# Schematic_Rev3_1.net
KiCad netlist of a schematic drawn in Altium Designer
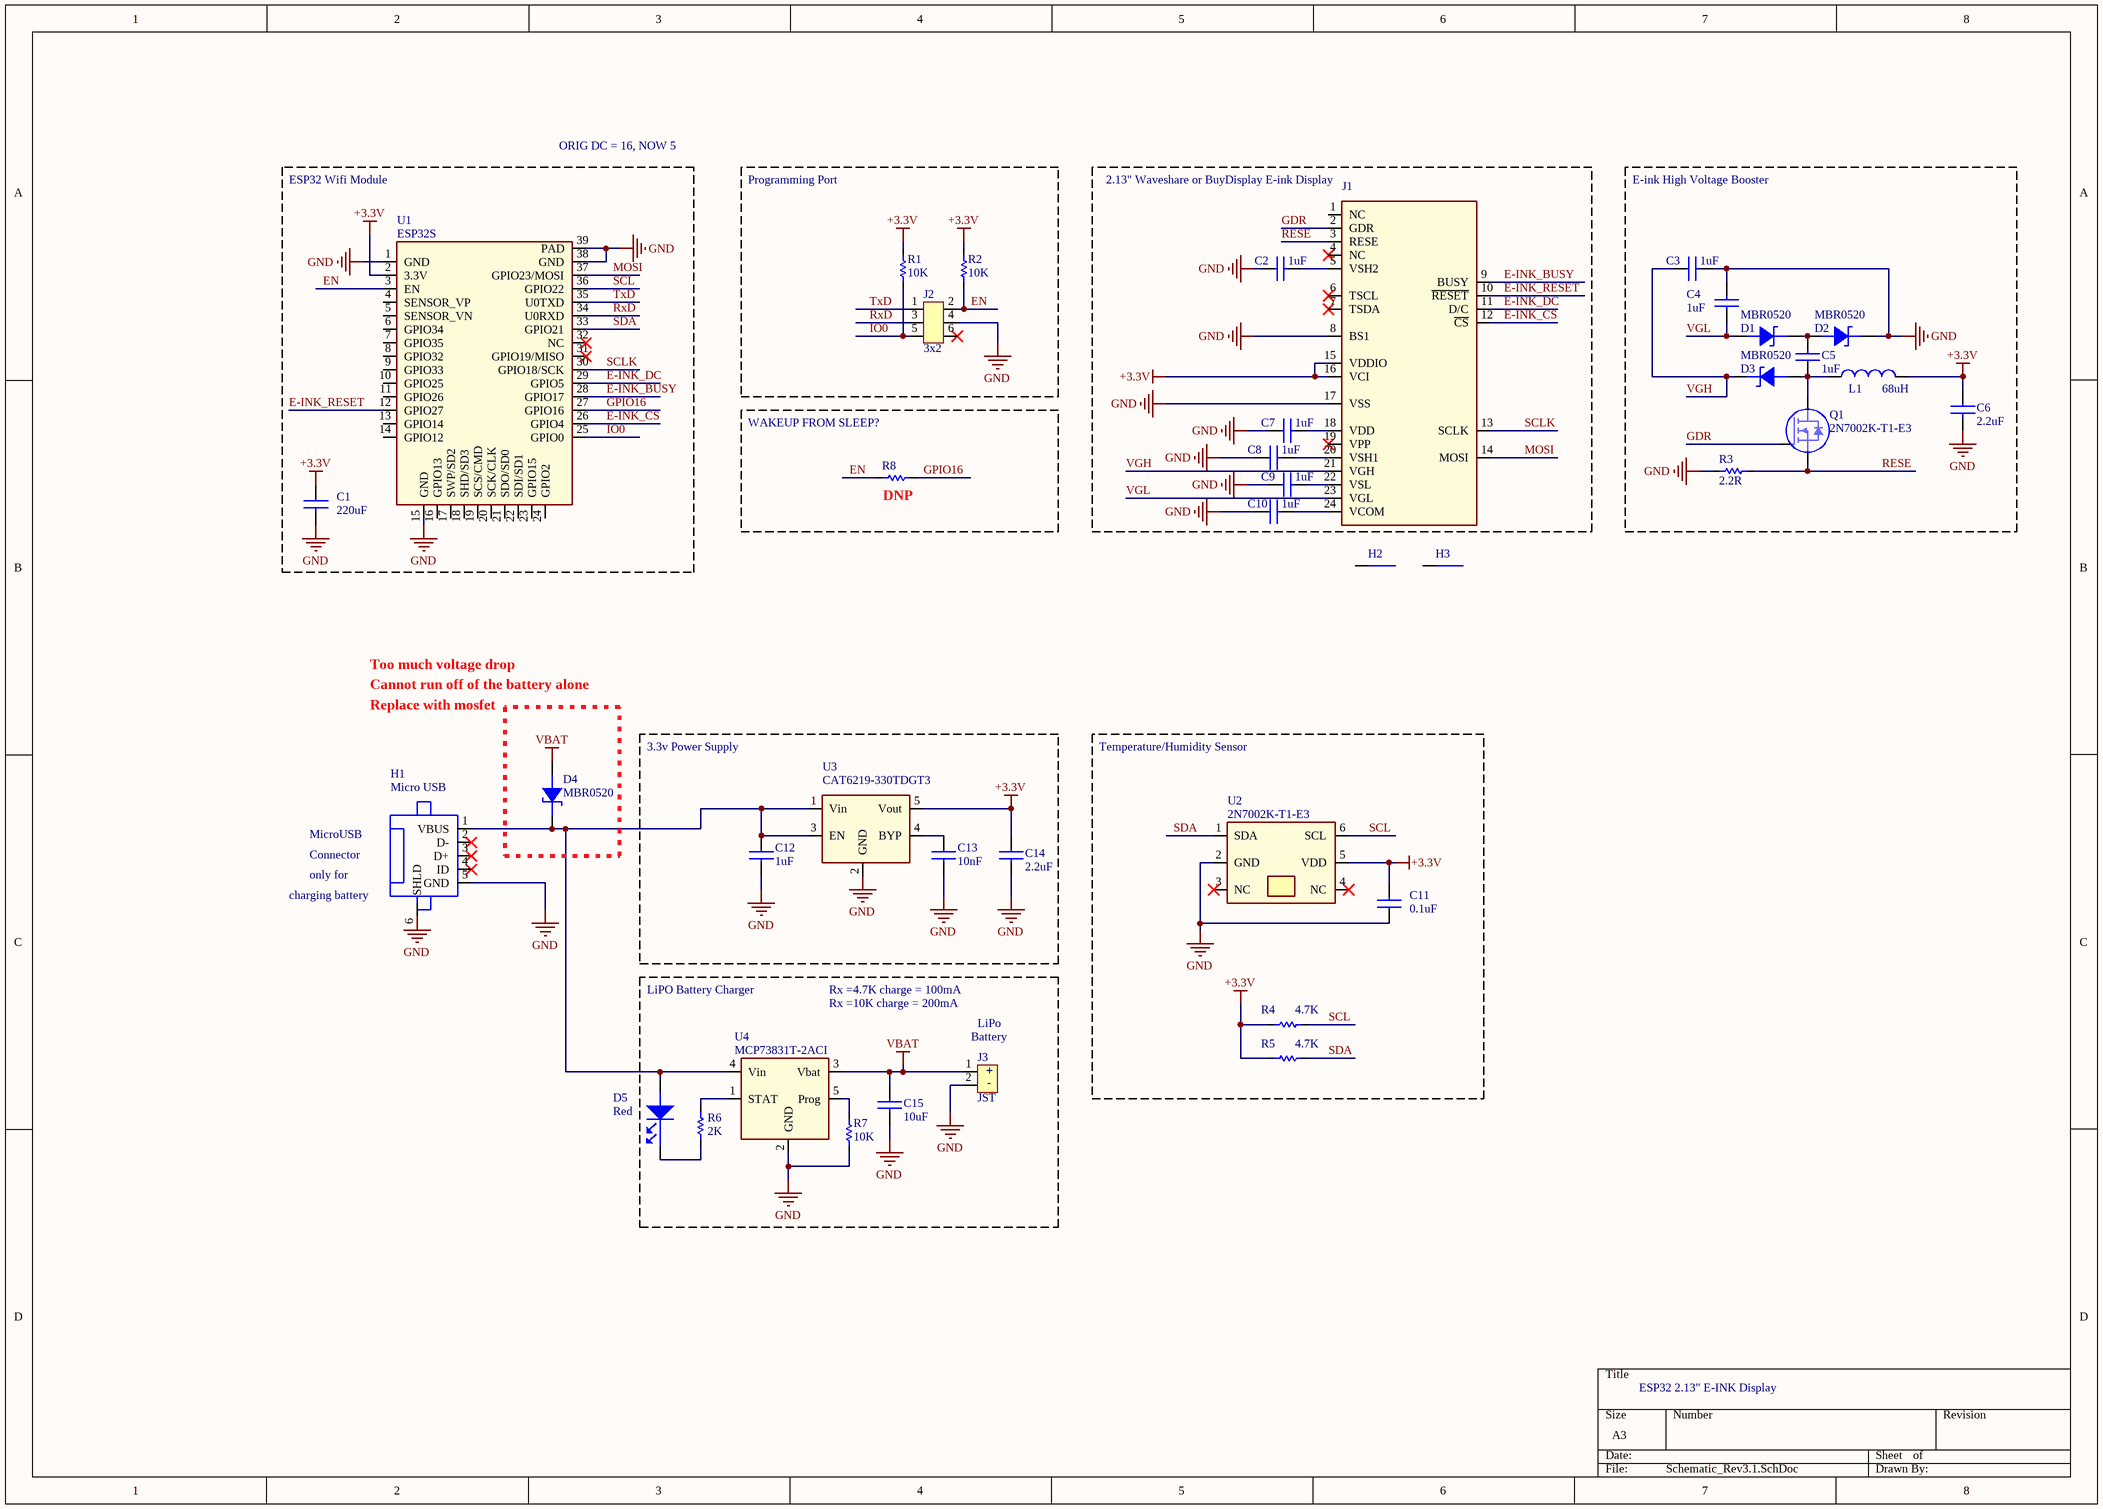
[diagram p0: Schematic_Rev3.1.SchDoc]

(export (version "E")
  (design (tool "Eeschema 10.0.6"))
  (components
    (comp (ref "C1")
      (value "220uF")
      (footprint "CAPC3216X160N")
      (description "CAP CER 220UF 4V X6S 1206")
      (fields (field (name "PARTNUMBER") "GRM31CC80G227ME11L") (field (name "MANUFACTURER") "Murata"))
      (libsource (lib "MAR") (part "CAP_1206"))
    )
    (comp (ref "C2")
      (value "1uF")
      (footprint "CAPC1608X09L")
      (description "CAP CER 1uF 16V X7R 0603")
      (fields (field (name "PARTNUMBER") "GRM188R71C105KA12D") (field (name "MANUFACTURER") "Murata"))
      (libsource (lib "MAR") (part "CAP_0603"))
    )
    (comp (ref "C3")
      (value "1uF")
      (footprint "CAPC1608X09L")
      (description "CAP CER 1UF 25V X7R 0603")
      (fields (field (name "PARTNUMBER") "C0603C105K3RACTU") (field (name "MANUFACTURER") "Kemet"))
      (libsource (lib "MAR") (part "CAP_0603"))
    )
    (comp (ref "C4")
      (value "1uF")
      (footprint "CAPC1608X09L")
      (description "CAP CER 1UF 25V X7R 0603")
      (fields (field (name "PARTNUMBER") "GRM188R71C105KA12D") (field (name "MANUFACTURER") "Kemet"))
      (libsource (lib "MAR") (part "CAP_0603"))
    )
    (comp (ref "C5")
      (value "1uF")
      (footprint "CAPC1608X09L")
      (description "CAP CER 1UF 25V X7R 0603")
      (fields (field (name "PARTNUMBER") "C0603C105K3RACTU") (field (name "MANUFACTURER") "Kemet"))
      (libsource (lib "MAR") (part "CAP_0603"))
    )
    (comp (ref "C6")
      (value "2.2uF")
      (footprint "CAPC1608X09L")
      (description "CAP CER 2.2uF 16V X5R 0603")
      (fields (field (name "MANUFACTURER") "Murata") (field (name "PARTNUMBER") "GRM188R61C225KE15D"))
      (libsource (lib "MAR") (part "CAP_0805"))
    )
    (comp (ref "C7")
      (value "1uF")
      (footprint "CAPC1608X09L")
      (description "CAP CER 1uF 16V X7R 0603")
      (fields (field (name "PARTNUMBER") "GRM188R71C105KA12D") (field (name "MANUFACTURER") "Murata"))
      (libsource (lib "MAR") (part "CAP_0603"))
    )
    (comp (ref "C8")
      (value "1uF")
      (footprint "CAPC1608X09L")
      (description "CAP CER 1uF 16V X7R 0603")
      (fields (field (name "PARTNUMBER") "GRM188R71C105KA12D") (field (name "MANUFACTURER") "Murata"))
      (libsource (lib "MAR") (part "CAP_0603"))
    )
    (comp (ref "C9")
      (value "1uF")
      (footprint "CAPC1608X09L")
      (description "CAP CER 1uF 16V X7R 0603")
      (fields (field (name "PARTNUMBER") "GRM188R71C105KA12D") (field (name "MANUFACTURER") "Murata"))
      (libsource (lib "MAR") (part "CAP_0603"))
    )
    (comp (ref "C10")
      (value "1uF")
      (footprint "CAPC1608X09L")
      (description "CAP CER 1uF 16V X7R 0603")
      (fields (field (name "PARTNUMBER") "GRM188R71C105KA12D") (field (name "MANUFACTURER") "Murata"))
      (libsource (lib "MAR") (part "CAP_0603"))
    )
    (comp (ref "C11")
      (value "0.1uF")
      (footprint "CAPC1608X09L")
      (description "CAP, 0.1uF, 25V, 0603")
      (fields (field (name "PARTNUMBER") "GRM188R71E104KA01D") (field (name "MANUFACTURER") "Murata"))
      (libsource (lib "MAR") (part "CAP_0603"))
    )
    (comp (ref "C12")
      (value "1uF")
      (footprint "CAPC1608X09L")
      (description "CAP CER 1uF 16V X7R 0603")
      (fields (field (name "PARTNUMBER") "GRM188R71C105KA12D") (field (name "MANUFACTURER") "Murata"))
      (libsource (lib "MAR") (part "CAP_0603"))
    )
    (comp (ref "C13")
      (value "10nF")
      (footprint "CAPC1608X09L")
      (description "CAP CER 0.01uF 16V X7R 0603")
      (fields (field (name "PARTNUMBER") "GRM188R71C103KA01D") (field (name "MANUFACTURER") "Murata"))
      (libsource (lib "MAR") (part "CAP_0603"))
    )
    (comp (ref "C14")
      (value "2.2uF")
      (footprint "CAPC1608X09L")
      (description "CAP CER 2.2uF 16V X5R 0603")
      (fields (field (name "MANUFACTURER") "Murata") (field (name "PARTNUMBER") "GRM188R61C225KE15D"))
      (libsource (lib "MAR") (part "CAP_0805"))
    )
    (comp (ref "C15")
      (value "10uF")
      (footprint "CAPC3216X160L")
      (description "CAP CER 10uF 16V 10% X7R 1206")
      (fields (field (name "PARTNUMBER") "CL31B106KOHNNNE") (field (name "MANUFACTURER") "Samsung"))
      (libsource (lib "MAR") (part "CAP_1206"))
    )
    (comp (ref "D1")
      (value "MBR0520")
      (footprint "SOD123")
      (description "DIODE SCHOTTKY 20V 500MA SOD123")
      (fields (field (name "MANUFACTURER") "Micro") (field (name "PARTNUMBER") "MBR0520-TP"))
      (libsource (lib "MAR") (part "MBR0520-TP"))
    )
    (comp (ref "D2")
      (value "MBR0520")
      (footprint "SOD123")
      (description "DIODE SCHOTTKY 20V 500MA SOD123")
      (fields (field (name "MANUFACTURER") "Micro") (field (name "PARTNUMBER") "MBR0520-TP"))
      (libsource (lib "MAR") (part "MBR0520-TP"))
    )
    (comp (ref "D3")
      (value "MBR0520")
      (footprint "SOD123")
      (description "DIODE SCHOTTKY 20V 500MA SOD123")
      (fields (field (name "MANUFACTURER") "Micro") (field (name "PARTNUMBER") "MBR0520-TP"))
      (libsource (lib "MAR") (part "MBR0520-TP"))
    )
    (comp (ref "D4")
      (value "MBR0520")
      (footprint "SOD123")
      (description "DIODE SCHOTTKY 20V 500MA SOD123")
      (fields (field (name "MANUFACTURER") "Micro") (field (name "PARTNUMBER") "MBR0520-TP"))
      (libsource (lib "MAR") (part "MBR0520-TP"))
    )
    (comp (ref "D5")
      (value "Red")
      (footprint "LED1608X55N-RED")
      (description "LED RED CLEAR 0603 SMD")
      (fields (field (name "MANUFACTURER") "Lite-On") (field (name "PARTNUMBER") "LTST-C191KRKT"))
      (libsource (lib "MAR") (part "LED_0603"))
    )
    (comp (ref "H1")
      (value "Micro USB")
      (footprint "1981584-1")
      (description "CONN RCPT MICRO USB TYPE AB")
      (fields (field (name "MANUFACTURER") "TE Connectivity") (field (name "PARTNUMBER") "1981584-1"))
      (libsource (lib "MAR") (part "1981584-1"))
    )
    (comp (ref "H2")
      (value "E-INK Display")
      (description "BuyDisplay 2.13\" E-INK Display")
      (fields (field (name "MANUFACTURER") "BuyDisplay") (field (name "PARTNUMBER") "ER-EPD0213-1"))
      (libsource (lib "MAR") (part "BOM_ITEM"))
    )
    (comp (ref "H3")
      (value "E-INK Display")
      (description "WaveShare 2.13\" E-INK Display")
      (fields (field (name "MANUFACTURER") "WaveShare") (field (name "PARTNUMBER") "13368"))
      (libsource (lib "MAR") (part "BOM_ITEM"))
    )
    (comp (ref "J1")
      (value "24POS Flex Con")
      (footprint "0524352471")
      (description "CONN FFC TOP 24POS 0.50MM R/A")
      (fields (field (name "MANUFACTURER") "Molex") (field (name "PARTNUMBER") "0524352471"))
      (libsource (lib "MAR") (part "0524352471"))
    )
    (comp (ref "J2")
      (value "3x2")
      (footprint "0872640652")
      (description "Recptacle, Female 3X2,TH, 2MM R/A")
      (fields (field (name "MANUFACTURER") "MOLEX") (field (name "PARTNUMBER") "0872640652"))
      (libsource (lib "MAR") (part "0872640652"))
    )
    (comp (ref "J3")
      (value "JST")
      (footprint "S2B-PH-K-S")
      (description "CONN HEADER PH SIDE 2POS 2MM")
      (fields (field (name "PARTNUMBER") "S2B-PH-K-S(LF)(SN)"))
      (libsource (lib "MAR") (part "S2B-PH-K-S(LF)(SN)"))
    )
    (comp (ref "L1")
      (value "68uH")
      (footprint "LHQ43C")
      (description "INDUCTOR 68UH 10% 220MA 1812")
      (fields (field (name "PARTNUMBER") "LQH43CN680K03L") (field (name "MANUFACTURER") "Murata"))
      (libsource (lib "MAR") (part "LQH43CN680K03L"))
    )
    (comp (ref "Q1")
      (value "2N7002K-T1-E3")
      (footprint "SOT95P240X110-3N")
      (description "MOSFET N-CH 60V 300MA SOT-23")
      (fields (field (name "MANUFACTURER") "Vishay Siliconix") (field (name "PARTNUMBER") "2N7002K-T1-E3"))
      (libsource (lib "MAR") (part "2N7002K-T1-E3"))
    )
    (comp (ref "R1")
      (value "10K")
      (footprint "RESC1608X06L")
      (description "RES SMD 10K OHM 1% 1/10W 0603")
      (fields (field (name "MANUFACTURER") "Panasonic") (field (name "PARTNUMBER") "ERJ-3EKF1002V"))
      (libsource (lib "MAR") (part "RES_0603"))
    )
    (comp (ref "R2")
      (value "10K")
      (footprint "RESC1608X06L")
      (description "RES SMD 10K OHM 1% 1/10W 0603")
      (fields (field (name "MANUFACTURER") "Panasonic") (field (name "PARTNUMBER") "ERJ-3EKF1002V"))
      (libsource (lib "MAR") (part "RES_0603"))
    )
    (comp (ref "R3")
      (value "2.2R")
      (footprint "RESC1608X06L")
      (description "RES SMD 2.2 OHM 5% 1/10W 0603")
      (fields (field (name "MANUFACTURER") "Panasonic") (field (name "PARTNUMBER") "ERJ-3GEYJ2R2V"))
      (libsource (lib "MAR") (part "RES_0603"))
    )
    (comp (ref "R4")
      (value "4.7K")
      (footprint "RESC1608X06L")
      (description "RES SMD 4.7K OHM 1% 1/4W 0603")
      (fields (field (name "MANUFACTURER") "Panasonic") (field (name "PARTNUMBER") "ERJ-PA3F4701V"))
      (libsource (lib "MAR") (part "RES_0603"))
    )
    (comp (ref "R5")
      (value "4.7K")
      (footprint "RESC1608X06L")
      (description "RES SMD 4.7K OHM 1% 1/4W 0603")
      (fields (field (name "MANUFACTURER") "Panasonic") (field (name "PARTNUMBER") "ERJ-PA3F4701V"))
      (libsource (lib "MAR") (part "RES_0603"))
    )
    (comp (ref "R6")
      (value "2K")
      (footprint "RESC1608X06L")
      (description "RES SMD 2K OHM 1% 1/10W 0603")
      (fields (field (name "MANUFACTURER") "Panasonic") (field (name "PARTNUMBER") "ERJ-3EKF2001V"))
      (libsource (lib "MAR") (part "RES_0603"))
    )
    (comp (ref "R7")
      (value "10K")
      (footprint "RESC1608X06L")
      (description "RES SMD 10K OHM 1% 1/10W 0603")
      (fields (field (name "MANUFACTURER") "Panasonic") (field (name "PARTNUMBER") "ERJ-3EKF1002V"))
      (libsource (lib "MAR") (part "RES_0603"))
    )
    (comp (ref "R8")
      (value "DNP")
      (footprint "RESC1608X06L")
      (description "RES 0603")
      (libsource (lib "MAR") (part "RES_0603"))
    )
    (comp (ref "U1")
      (value "ESP32s")
      (footprint "ESP32")
      (description "WIFI&Bluetooth")
      (fields (field (name "PARTNUMBER") "ESP32S"))
      (libsource (lib "MAR") (part "ESP32"))
    )
    (comp (ref "U2")
      (value "HDC1080DMBT")
      (footprint "S-PWSON-N6")
      (description "Humidity/Temperature Sensor")
      (fields (field (name "MANUFACTURER") "Texas Instruments") (field (name "PARTNUMBER") "2N7002K-T1-E3"))
      (libsource (lib "MAR") (part "HDC1080DMBT"))
    )
    (comp (ref "U3")
      (value "CAT6219-330TDGT3")
      (footprint "SOT95P280X144-5N")
      (description "IC REG LDO 3.3V 0.5A SOT23-5")
      (fields (field (name "MANUFACTURER") "On Semi"))
      (libsource (lib "MAR") (part "CAT6219-330TDGT3"))
    )
    (comp (ref "U4")
      (value "MCP73831T-2ACI")
      (footprint "SOT95P280X144-5N")
      (description "Charger IC Lithium-Ion/Polymer SOT23-5")
      (fields (field (name "MANUFACTURER") "Microchip") (field (name "PARTNUMBER") "MCP73831T-2ACI/OT"))
      (libsource (lib "MAR") (part "MCP73831T-2ACI/OT"))
    )
  )
  (nets
    (net (code "1") (name "+3.3V") (class "Default")
      (node (ref "C1") (pin "1") (pinfunction "1_1") (pintype "passive"))
      (node (ref "C11") (pin "2") (pinfunction "2_2") (pintype "passive"))
      (node (ref "C14") (pin "1") (pinfunction "1_1") (pintype "passive"))
      (node (ref "C6") (pin "1") (pinfunction "1_1") (pintype "passive"))
      (node (ref "J1") (pin "15") (pinfunction "VDDIO_15") (pintype "power_in"))
      (node (ref "J1") (pin "16") (pinfunction "VCI_16") (pintype "power_in"))
      (node (ref "L1") (pin "2") (pinfunction "2_2") (pintype "passive"))
      (node (ref "R1") (pin "1") (pintype "passive"))
      (node (ref "R2") (pin "1") (pintype "passive"))
      (node (ref "R4") (pin "2") (pintype "passive"))
      (node (ref "R5") (pin "2") (pintype "passive"))
      (node (ref "U1") (pin "2") (pinfunction "3.3V_2") (pintype "power_in"))
      (node (ref "U2") (pin "5") (pinfunction "VDD_5") (pintype "power_in"))
      (node (ref "U3") (pin "5") (pinfunction "Vout_5") (pintype "passive"))
    )
    (net (code "2") (name "/E-INK_BUSY") (class "Default")
      (node (ref "J1") (pin "9") (pinfunction "BUSY_9") (pintype "passive"))
      (node (ref "U1") (pin "28") (pinfunction "GPIO17_28") (pintype "passive"))
    )
    (net (code "3") (name "/E-INK_CS") (class "Default")
      (node (ref "J1") (pin "12") (pinfunction "~{CS}_12") (pintype "passive"))
      (node (ref "U1") (pin "26") (pinfunction "GPIO4_26") (pintype "passive"))
    )
    (net (code "4") (name "/E-INK_DC") (class "Default")
      (node (ref "J1") (pin "11") (pinfunction "D/C_11") (pintype "passive"))
      (node (ref "U1") (pin "29") (pinfunction "GPIO5_29") (pintype "passive"))
    )
    (net (code "5") (name "/E-INK_RESET") (class "Default")
      (node (ref "J1") (pin "10") (pinfunction "~{RESET}_10") (pintype "passive"))
      (node (ref "U1") (pin "12") (pinfunction "GPIO27_12") (pintype "passive"))
    )
    (net (code "6") (name "/EN") (class "Default")
      (node (ref "J2") (pin "2") (pintype "passive"))
      (node (ref "R2") (pin "2") (pintype "passive"))
      (node (ref "R8") (pin "1") (pintype "passive"))
      (node (ref "U1") (pin "3") (pinfunction "EN_3") (pintype "passive"))
    )
    (net (code "7") (name "/GDR") (class "Default")
      (node (ref "J1") (pin "2") (pinfunction "GDR_2") (pintype "passive"))
      (node (ref "Q1") (pin "1") (pinfunction "G_1") (pintype "passive"))
    )
    (net (code "8") (name "/GPIO16") (class "Default")
      (node (ref "R8") (pin "2") (pintype "passive"))
      (node (ref "U1") (pin "27") (pinfunction "GPIO16_27") (pintype "passive"))
    )
    (net (code "9") (name "/IO0") (class "Default")
      (node (ref "J2") (pin "5") (pintype "passive"))
      (node (ref "R1") (pin "2") (pintype "passive"))
      (node (ref "U1") (pin "25") (pinfunction "GPIO0_25") (pintype "passive"))
    )
    (net (code "10") (name "/MOSI") (class "Default")
      (node (ref "J1") (pin "14") (pinfunction "MOSI_14") (pintype "passive"))
      (node (ref "U1") (pin "37") (pinfunction "GPIO23/MOSI_37") (pintype "passive"))
    )
    (net (code "11") (name "/RESE") (class "Default")
      (node (ref "J1") (pin "3") (pinfunction "RESE_3") (pintype "passive"))
      (node (ref "Q1") (pin "2") (pinfunction "S_2") (pintype "passive"))
      (node (ref "R3") (pin "2") (pintype "passive"))
    )
    (net (code "12") (name "/RxD") (class "Default")
      (node (ref "J2") (pin "3") (pintype "passive"))
      (node (ref "U1") (pin "34") (pinfunction "U0RXD_34") (pintype "passive"))
    )
    (net (code "13") (name "/SCL") (class "Default")
      (node (ref "R4") (pin "1") (pintype "passive"))
      (node (ref "U1") (pin "36") (pinfunction "GPIO22_36") (pintype "passive"))
      (node (ref "U2") (pin "6") (pinfunction "SCL_6") (pintype "passive"))
    )
    (net (code "14") (name "/SCLK") (class "Default")
      (node (ref "J1") (pin "13") (pinfunction "SCLK_13") (pintype "passive"))
      (node (ref "U1") (pin "30") (pinfunction "GPIO18/SCK_30") (pintype "passive"))
    )
    (net (code "15") (name "/SDA") (class "Default")
      (node (ref "R5") (pin "1") (pintype "passive"))
      (node (ref "U1") (pin "33") (pinfunction "GPIO21_33") (pintype "passive"))
      (node (ref "U2") (pin "1") (pinfunction "SDA_1") (pintype "passive"))
    )
    (net (code "16") (name "/TxD") (class "Default")
      (node (ref "J2") (pin "1") (pintype "passive"))
      (node (ref "U1") (pin "35") (pinfunction "U0TXD_35") (pintype "passive"))
    )
    (net (code "17") (name "/VGH") (class "Default")
      (node (ref "C3") (pin "1") (pinfunction "1_1") (pintype "passive"))
      (node (ref "D3") (pin "1") (pinfunction "Cathode_1") (pintype "passive"))
      (node (ref "J1") (pin "21") (pinfunction "VGH_21") (pintype "passive"))
    )
    (net (code "18") (name "/VGL") (class "Default")
      (node (ref "C4") (pin "1") (pinfunction "1_1") (pintype "passive"))
      (node (ref "D1") (pin "2") (pinfunction "Annode_2") (pintype "passive"))
      (node (ref "J1") (pin "23") (pinfunction "VGL_23") (pintype "passive"))
    )
    (net (code "19") (name "GND") (class "Default")
      (node (ref "C1") (pin "2") (pinfunction "2_2") (pintype "passive"))
      (node (ref "C10") (pin "1") (pinfunction "1_1") (pintype "passive"))
      (node (ref "C11") (pin "1") (pinfunction "1_1") (pintype "passive"))
      (node (ref "C12") (pin "2") (pinfunction "2_2") (pintype "passive"))
      (node (ref "C13") (pin "2") (pinfunction "2_2") (pintype "passive"))
      (node (ref "C14") (pin "2") (pinfunction "2_2") (pintype "passive"))
      (node (ref "C15") (pin "2") (pinfunction "2_2") (pintype "passive"))
      (node (ref "C2") (pin "1") (pinfunction "1_1") (pintype "passive"))
      (node (ref "C3") (pin "2") (pinfunction "2_2") (pintype "passive"))
      (node (ref "C4") (pin "2") (pinfunction "2_2") (pintype "passive"))
      (node (ref "C6") (pin "2") (pinfunction "2_2") (pintype "passive"))
      (node (ref "C7") (pin "1") (pinfunction "1_1") (pintype "passive"))
      (node (ref "C8") (pin "1") (pinfunction "1_1") (pintype "passive"))
      (node (ref "C9") (pin "1") (pinfunction "1_1") (pintype "passive"))
      (node (ref "D2") (pin "1") (pinfunction "Cathode_1") (pintype "passive"))
      (node (ref "H1") (pin "5") (pinfunction "GND_5") (pintype "power_in"))
      (node (ref "H1") (pin "6") (pinfunction "SHLD_6") (pintype "power_in"))
      (node (ref "J1") (pin "17") (pinfunction "VSS_17") (pintype "power_in"))
      (node (ref "J1") (pin "8") (pinfunction "BS1_8") (pintype "passive"))
      (node (ref "J2") (pin "4") (pintype "passive"))
      (node (ref "J3") (pin "2") (pintype "passive"))
      (node (ref "R3") (pin "1") (pintype "passive"))
      (node (ref "R7") (pin "2") (pintype "passive"))
      (node (ref "U1") (pin "1") (pinfunction "GND_1") (pintype "power_in"))
      (node (ref "U1") (pin "15") (pinfunction "GND_15") (pintype "passive"))
      (node (ref "U1") (pin "38") (pinfunction "GND_38") (pintype "power_in"))
      (node (ref "U1") (pin "39") (pinfunction "PAD_39") (pintype "passive"))
      (node (ref "U2") (pin "2") (pinfunction "GND_2") (pintype "power_in"))
      (node (ref "U3") (pin "2") (pinfunction "GND_2") (pintype "power_in"))
      (node (ref "U4") (pin "2") (pinfunction "GND_2") (pintype "power_in"))
    )
    (net (code "20") (name "Net-(D1-Cathode)") (class "Default")
      (node (ref "C5") (pin "2") (pinfunction "2_2") (pintype "passive"))
      (node (ref "D1") (pin "1") (pinfunction "Cathode_1") (pintype "passive"))
      (node (ref "D2") (pin "2") (pinfunction "Annode_2") (pintype "passive"))
    )
    (net (code "21") (name "Net-(D3-Annode)") (class "Default")
      (node (ref "C5") (pin "1") (pinfunction "1_1") (pintype "passive"))
      (node (ref "D3") (pin "2") (pinfunction "Annode_2") (pintype "passive"))
      (node (ref "L1") (pin "1") (pinfunction "1_1") (pintype "passive"))
      (node (ref "Q1") (pin "3") (pinfunction "D_3") (pintype "passive"))
    )
    (net (code "22") (name "Net-(D4-Cathode)") (class "Default")
      (node (ref "C12") (pin "1") (pinfunction "1_1") (pintype "passive"))
      (node (ref "D4") (pin "1") (pinfunction "Cathode_1") (pintype "passive"))
      (node (ref "D5") (pin "2") (pinfunction "ANODE_2") (pintype "passive"))
      (node (ref "H1") (pin "1") (pinfunction "VBUS_1") (pintype "power_in"))
      (node (ref "U3") (pin "1") (pinfunction "Vin_1") (pintype "passive"))
      (node (ref "U3") (pin "3") (pinfunction "EN_3") (pintype "passive"))
      (node (ref "U4") (pin "4") (pinfunction "Vin_4") (pintype "passive"))
    )
    (net (code "23") (name "Net-(D5-CATHODE)") (class "Default")
      (node (ref "D5") (pin "1") (pinfunction "CATHODE_1") (pintype "passive"))
      (node (ref "R6") (pin "1") (pintype "passive"))
    )
    (net (code "24") (name "Net-(J1-VCOM)") (class "Default")
      (node (ref "C10") (pin "2") (pinfunction "2_2") (pintype "passive"))
      (node (ref "J1") (pin "24") (pinfunction "VCOM_24") (pintype "passive"))
    )
    (net (code "25") (name "Net-(J1-VDD)") (class "Default")
      (node (ref "C7") (pin "2") (pinfunction "2_2") (pintype "passive"))
      (node (ref "J1") (pin "18") (pinfunction "VDD_18") (pintype "power_in"))
    )
    (net (code "26") (name "Net-(J1-VSH1)") (class "Default")
      (node (ref "C8") (pin "2") (pinfunction "2_2") (pintype "passive"))
      (node (ref "J1") (pin "20") (pinfunction "VSH1_20") (pintype "passive"))
    )
    (net (code "27") (name "Net-(J1-VSH2)") (class "Default")
      (node (ref "C2") (pin "2") (pinfunction "2_2") (pintype "passive"))
      (node (ref "J1") (pin "5") (pinfunction "VSH2_5") (pintype "passive"))
    )
    (net (code "28") (name "Net-(J1-VSL)") (class "Default")
      (node (ref "C9") (pin "2") (pinfunction "2_2") (pintype "passive"))
      (node (ref "J1") (pin "22") (pinfunction "VSL_22") (pintype "passive"))
    )
    (net (code "29") (name "Net-(U3-BYP)") (class "Default")
      (node (ref "C13") (pin "1") (pinfunction "1_1") (pintype "passive"))
      (node (ref "U3") (pin "4") (pinfunction "BYP_4") (pintype "passive"))
    )
    (net (code "30") (name "Net-(U4-Prog)") (class "Default")
      (node (ref "R7") (pin "1") (pintype "passive"))
      (node (ref "U4") (pin "5") (pinfunction "Prog_5") (pintype "passive"))
    )
    (net (code "31") (name "Net-(U4-STAT)") (class "Default")
      (node (ref "R6") (pin "2") (pintype "passive"))
      (node (ref "U4") (pin "1") (pinfunction "STAT_1") (pintype "passive"))
    )
    (net (code "32") (name "VBAT") (class "Default")
      (node (ref "C15") (pin "1") (pinfunction "1_1") (pintype "passive"))
      (node (ref "D4") (pin "2") (pinfunction "Annode_2") (pintype "passive"))
      (node (ref "J3") (pin "1") (pintype "passive"))
      (node (ref "U4") (pin "3") (pinfunction "Vbat_3") (pintype "passive"))
    )
    (net (code "33") (name "unconnected-(H1-D+-Pad3)") (class "Default")
      (node (ref "H1") (pin "3") (pinfunction "D+_3") (pintype "passive+no_connect"))
    )
    (net (code "34") (name "unconnected-(H1-D--Pad2)") (class "Default")
      (node (ref "H1") (pin "2") (pinfunction "D-_2") (pintype "passive+no_connect"))
    )
    (net (code "35") (name "unconnected-(H1-ID-Pad4)") (class "Default")
      (node (ref "H1") (pin "4") (pinfunction "ID_4") (pintype "passive+no_connect"))
    )
    (net (code "36") (name "unconnected-(H2-Pad)") (class "Default")
      (node (ref "H2") (pin "") (pintype "passive"))
    )
    (net (code "37") (name "unconnected-(H3-Pad)") (class "Default")
      (node (ref "H3") (pin "") (pintype "passive"))
    )
    (net (code "38") (name "unconnected-(J1-NC-Pad1)") (class "Default")
      (node (ref "J1") (pin "1") (pinfunction "NC_1") (pintype "passive"))
    )
    (net (code "39") (name "unconnected-(J1-NC-Pad4)") (class "Default")
      (node (ref "J1") (pin "4") (pinfunction "NC_4") (pintype "passive+no_connect"))
    )
    (net (code "40") (name "unconnected-(J1-TSCL-Pad6)") (class "Default")
      (node (ref "J1") (pin "6") (pinfunction "TSCL_6") (pintype "passive+no_connect"))
    )
    (net (code "41") (name "unconnected-(J1-TSDA-Pad7)") (class "Default")
      (node (ref "J1") (pin "7") (pinfunction "TSDA_7") (pintype "passive+no_connect"))
    )
    (net (code "42") (name "unconnected-(J1-VPP-Pad19)") (class "Default")
      (node (ref "J1") (pin "19") (pinfunction "VPP_19") (pintype "passive+no_connect"))
    )
    (net (code "43") (name "unconnected-(J2-Pad6)") (class "Default")
      (node (ref "J2") (pin "6") (pintype "passive+no_connect"))
    )
    (net (code "44") (name "unconnected-(U1-GPIO2-Pad24)") (class "Default")
      (node (ref "U1") (pin "24") (pinfunction "GPIO2_24") (pintype "passive"))
    )
    (net (code "45") (name "unconnected-(U1-GPIO12-Pad14)") (class "Default")
      (node (ref "U1") (pin "14") (pinfunction "GPIO12_14") (pintype "passive"))
    )
    (net (code "46") (name "unconnected-(U1-GPIO13-Pad16)") (class "Default")
      (node (ref "U1") (pin "16") (pinfunction "GPIO13_16") (pintype "passive"))
    )
    (net (code "47") (name "unconnected-(U1-GPIO14-Pad13)") (class "Default")
      (node (ref "U1") (pin "13") (pinfunction "GPIO14_13") (pintype "passive"))
    )
    (net (code "48") (name "unconnected-(U1-GPIO15-Pad23)") (class "Default")
      (node (ref "U1") (pin "23") (pinfunction "GPIO15_23") (pintype "passive"))
    )
    (net (code "49") (name "unconnected-(U1-GPIO19{slash}MISO-Pad31)") (class "Default")
      (node (ref "U1") (pin "31") (pinfunction "GPIO19/MISO_31") (pintype "passive+no_connect"))
    )
    (net (code "50") (name "unconnected-(U1-GPIO25-Pad10)") (class "Default")
      (node (ref "U1") (pin "10") (pinfunction "GPIO25_10") (pintype "passive"))
    )
    (net (code "51") (name "unconnected-(U1-GPIO26-Pad11)") (class "Default")
      (node (ref "U1") (pin "11") (pinfunction "GPIO26_11") (pintype "passive"))
    )
    (net (code "52") (name "unconnected-(U1-GPIO32-Pad8)") (class "Default")
      (node (ref "U1") (pin "8") (pinfunction "GPIO32_8") (pintype "passive"))
    )
    (net (code "53") (name "unconnected-(U1-GPIO33-Pad9)") (class "Default")
      (node (ref "U1") (pin "9") (pinfunction "GPIO33_9") (pintype "passive"))
    )
    (net (code "54") (name "unconnected-(U1-GPIO34-Pad6)") (class "Default")
      (node (ref "U1") (pin "6") (pinfunction "GPIO34_6") (pintype "passive"))
    )
    (net (code "55") (name "unconnected-(U1-GPIO35-Pad7)") (class "Default")
      (node (ref "U1") (pin "7") (pinfunction "GPIO35_7") (pintype "passive"))
    )
    (net (code "56") (name "unconnected-(U1-NC-Pad32)") (class "Default")
      (node (ref "U1") (pin "32") (pinfunction "NC_32") (pintype "passive+no_connect"))
    )
    (net (code "57") (name "unconnected-(U1-SCK{slash}CLK-Pad20)") (class "Default")
      (node (ref "U1") (pin "20") (pinfunction "SCK/CLK_20") (pintype "passive"))
    )
    (net (code "58") (name "unconnected-(U1-SCS{slash}CMD-Pad19)") (class "Default")
      (node (ref "U1") (pin "19") (pinfunction "SCS/CMD_19") (pintype "passive"))
    )
    (net (code "59") (name "unconnected-(U1-SDI{slash}SD1-Pad22)") (class "Default")
      (node (ref "U1") (pin "22") (pinfunction "SDI/SD1_22") (pintype "passive"))
    )
    (net (code "60") (name "unconnected-(U1-SDO{slash}SD0-Pad21)") (class "Default")
      (node (ref "U1") (pin "21") (pinfunction "SDO/SD0_21") (pintype "passive"))
    )
    (net (code "61") (name "unconnected-(U1-SENSOR_VN-Pad5)") (class "Default")
      (node (ref "U1") (pin "5") (pinfunction "SENSOR_VN_5") (pintype "passive"))
    )
    (net (code "62") (name "unconnected-(U1-SENSOR_VP-Pad4)") (class "Default")
      (node (ref "U1") (pin "4") (pinfunction "SENSOR_VP_4") (pintype "passive"))
    )
    (net (code "63") (name "unconnected-(U1-SHD{slash}SD3-Pad18)") (class "Default")
      (node (ref "U1") (pin "18") (pinfunction "SHD/SD3_18") (pintype "passive"))
    )
    (net (code "64") (name "unconnected-(U1-SWP{slash}SD2-Pad17)") (class "Default")
      (node (ref "U1") (pin "17") (pinfunction "SWP/SD2_17") (pintype "passive"))
    )
    (net (code "65") (name "unconnected-(U2-NC-Pad3)") (class "Default")
      (node (ref "U2") (pin "3") (pinfunction "NC_3") (pintype "passive+no_connect"))
    )
    (net (code "66") (name "unconnected-(U2-NC-Pad4)") (class "Default")
      (node (ref "U2") (pin "4") (pinfunction "NC_4") (pintype "passive+no_connect"))
    )
  )
)
